# USB_TTL_CH340B.net
KiCad netlist of a schematic drawn in EasyEDA Pro
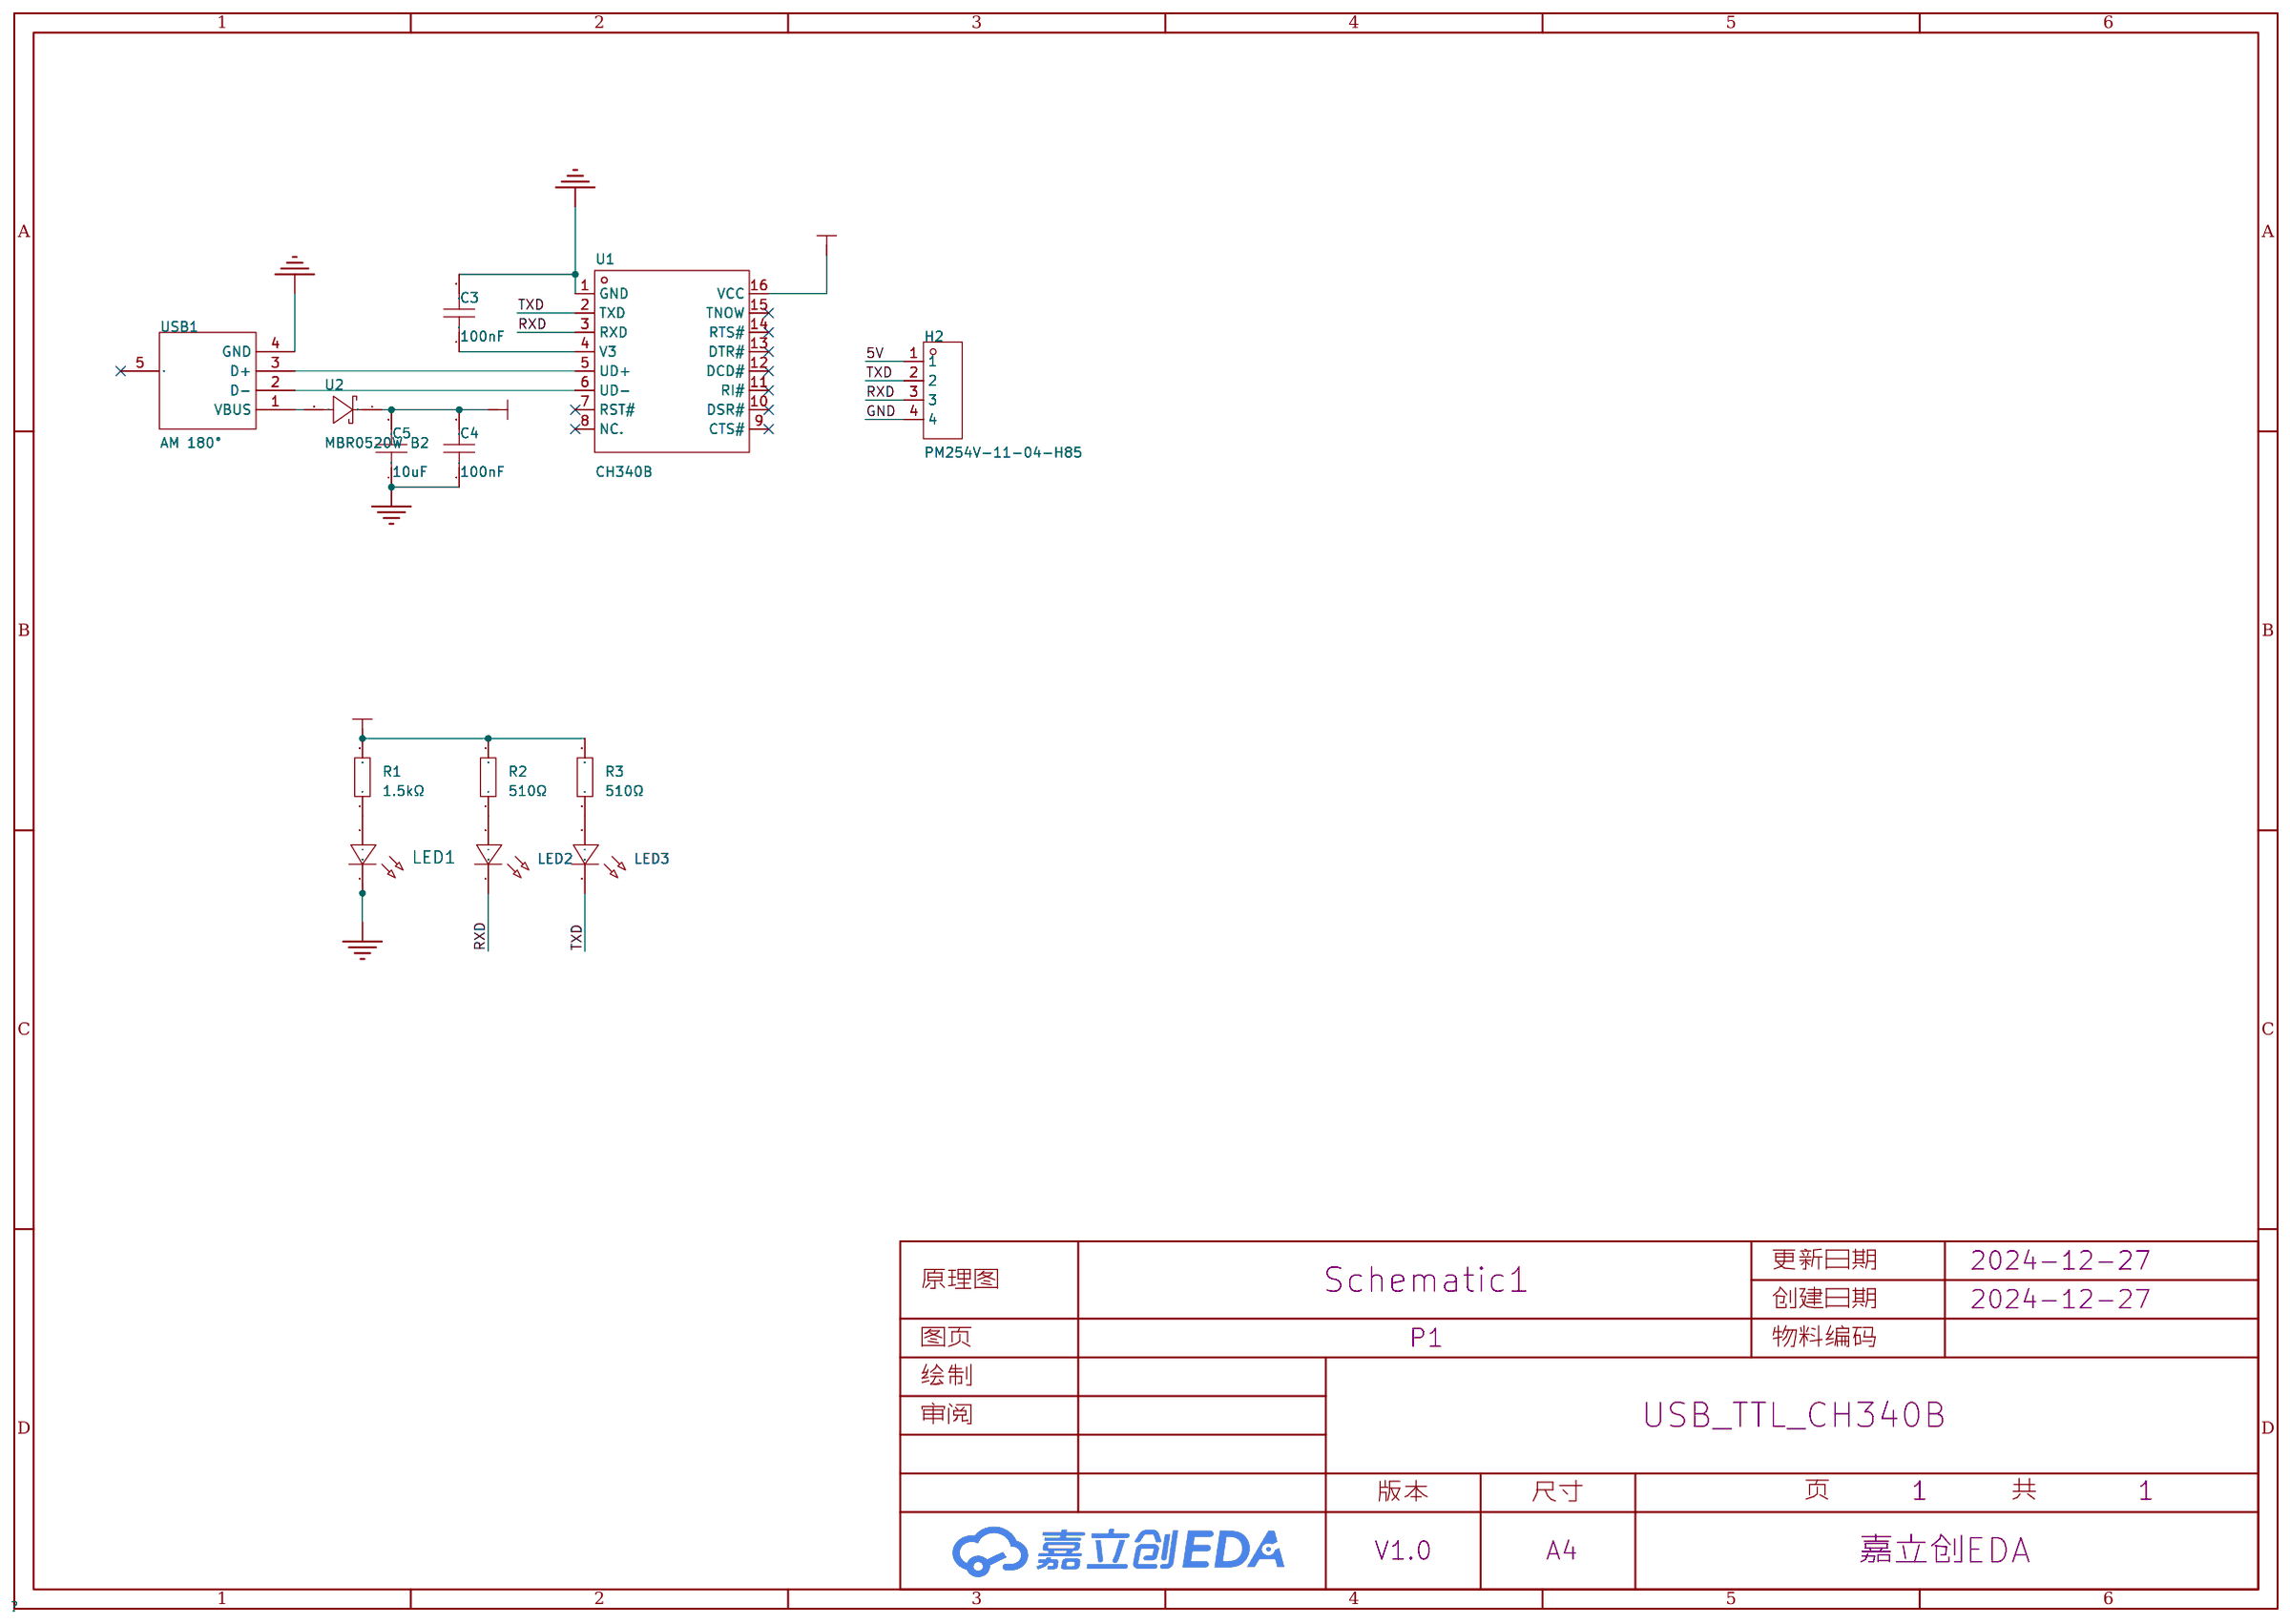
[diagram p0: schematic sheet]

(export (version "E")
  (design (tool "Eeschema 10.0.6"))
  (components
    (comp (ref "C3")
      (value "100nF")
      (footprint "easyedapro:C0603")
      (description "容值:100nF;精度:±10%;额定电压:50V;材质(温度系数):X7R;")
      (fields
        (field (name "Manufacturer Part") "CC0603KRX7R9BB104")
        (field (name "Manufacturer") "YAGEO(国巨)")
      )
      (libsource (lib "easyedapro") (part "CC0603KRX7R9BB104"))
    )
    (comp (ref "C4")
      (value "100nF")
      (footprint "easyedapro:C0603")
      (description "容值:100nF;精度:±10%;额定电压:50V;材质(温度系数):X7R;")
      (fields
        (field (name "Manufacturer Part") "CC0603KRX7R9BB104")
        (field (name "Manufacturer") "YAGEO(国巨)")
      )
      (libsource (lib "easyedapro") (part "CC0603KRX7R9BB104"))
    )
    (comp (ref "C5")
      (value "10uF")
      (footprint "easyedapro:C0603")
      (description "容值:100nF;精度:±10%;额定电压:50V;材质(温度系数):X7R;")
      (fields
        (field (name "Manufacturer Part") "CC0603KRX7R9BB104")
        (field (name "Manufacturer") "YAGEO(国巨)")
      )
      (libsource (lib "easyedapro") (part "CC0603KRX7R9BB104"))
    )
    (comp (ref "H2")
      (value "PM254V-11-04-H85")
      (footprint "easyedapro:HDR-TH_4P-P2.54-V-F")
      (description "间距:2.54mm;总孔位数:4;排数:1;插孔结构:1x4P;行距:-;安装类型:直插;塑高:-;触头材质:黄铜;触头镀层:-;")
      (fields (field (name "Manufacturer") "XFCN(兴飞)"))
      (libsource (lib "easyedapro") (part "PM254V-11-04-H85"))
    )
    (comp (ref "LED1")
      (value "~")
      (footprint "easyedapro:LED_0603")
      (libsource (lib "easyedapro") (part "LED_R"))
    )
    (comp (ref "LED2")
      (value "~")
      (footprint "easyedapro:LED_0603")
      (libsource (lib "easyedapro") (part "LED_G"))
    )
    (comp (ref "LED3")
      (value "~")
      (footprint "easyedapro:LED_0603")
      (libsource (lib "easyedapro") (part "LED_B"))
    )
    (comp (ref "R1")
      (value "1.5kΩ")
      (footprint "easyedapro:R0603")
      (description "电阻类型:厚膜电阻;阻值:1.5kΩ;精度:±1%;功率:100mW;最大工作电压:75V;温度系数:±100ppm/°C;")
      (fields (field (name "Manufacturer Part") "AF0603FR-071K5L") (field (name "Manufacturer") "YAGEO(国巨)"))
      (libsource (lib "easyedapro") (part "AF0603FR-071K5L"))
    )
    (comp (ref "R2")
      (value "510Ω")
      (footprint "easyedapro:R0603")
      (description "电阻类型:厚膜电阻;阻值:1.5kΩ;精度:±1%;功率:100mW;最大工作电压:75V;温度系数:±100ppm/°C;")
      (fields (field (name "Manufacturer Part") "AF0603FR-071K5L") (field (name "Manufacturer") "YAGEO(国巨)"))
      (libsource (lib "easyedapro") (part "AF0603FR-071K5L"))
    )
    (comp (ref "R3")
      (value "510Ω")
      (footprint "easyedapro:R0603")
      (description "电阻类型:厚膜电阻;阻值:1.5kΩ;精度:±1%;功率:100mW;最大工作电压:75V;温度系数:±100ppm/°C;")
      (fields (field (name "Manufacturer Part") "AF0603FR-071K5L") (field (name "Manufacturer") "YAGEO(国巨)"))
      (libsource (lib "easyedapro") (part "AF0603FR-071K5L"))
    )
    (comp (ref "U1")
      (value "CH340B")
      (footprint "easyedapro:SOIC-16_L9.9-W3.9-P1.27-LS6.0-BL")
      (description "应用功能:收发器;接口协议:USB 2.0;数据速率:2Mbps;")
      (fields (field (name "Manufacturer") "WCH(南京沁恒)"))
      (libsource (lib "easyedapro") (part "CH340B"))
    )
    (comp (ref "U2")
      (value "MBR0520W B2")
      (footprint "easyedapro:SOD-123_L2.7-W1.7-LS3.8-RD")
      (fields (field (name "Manufacturer") "Slkor(萨科微)"))
      (libsource (lib "easyedapro") (part "MBR0520W B2"))
    )
    (comp (ref "USB1")
      (value "AM 180°")
      (footprint "easyedapro:USB-SMD_AM180")
      (description "连接器类型:Type-A;标准:USB 2.0;公母:公;安装方式:卧贴;触点数量:4P;端口数量:1;额定电流 - 电源:1.5A;工作温度范围:-25°C~+85°C;")
      (fields (field (name "Manufacturer") "SHOU HAN(首韩)"))
      (libsource (lib "easyedapro") (part "AM 180°"))
    )
  )
  (nets
    (net (code "1") (name "/RXD") (class "Default")
      (node (ref "H2") (pin "3") (pinfunction "3_3") (pintype "input"))
      (node (ref "LED2") (pin "1") (pinfunction "C_1") (pintype "input"))
      (node (ref "U1") (pin "3") (pinfunction "RXD_3") (pintype "unspecified"))
    )
    (net (code "2") (name "/TXD") (class "Default")
      (node (ref "H2") (pin "2") (pinfunction "2_2") (pintype "input"))
      (node (ref "LED3") (pin "1") (pinfunction "C_1") (pintype "input"))
      (node (ref "U1") (pin "2") (pinfunction "TXD_2") (pintype "unspecified"))
    )
    (net (code "3") (name "5V") (class "Default")
      (node (ref "C4") (pin "2") (pinfunction "2_2") (pintype "unspecified"))
      (node (ref "C5") (pin "2") (pinfunction "2_2") (pintype "unspecified"))
      (node (ref "H2") (pin "1") (pinfunction "1_1") (pintype "input"))
      (node (ref "R1") (pin "2") (pinfunction "2_2") (pintype "input"))
      (node (ref "R2") (pin "2") (pinfunction "2_2") (pintype "input"))
      (node (ref "R3") (pin "2") (pinfunction "2_2") (pintype "input"))
      (node (ref "U1") (pin "16") (pinfunction "VCC_16") (pintype "unspecified"))
      (node (ref "U2") (pin "1") (pinfunction "C_1") (pintype "unspecified"))
    )
    (net (code "4") (name "GND") (class "Default")
      (node (ref "C3") (pin "2") (pinfunction "2_2") (pintype "unspecified"))
      (node (ref "C4") (pin "1") (pinfunction "1_1") (pintype "unspecified"))
      (node (ref "C5") (pin "1") (pinfunction "1_1") (pintype "unspecified"))
      (node (ref "H2") (pin "4") (pinfunction "4_4") (pintype "input"))
      (node (ref "LED1") (pin "1") (pinfunction "C_1") (pintype "input"))
      (node (ref "U1") (pin "1") (pinfunction "GND_1") (pintype "unspecified"))
      (node (ref "USB1") (pin "4") (pinfunction "GND_4") (pintype "input"))
    )
    (net (code "5") (name "Net-(LED1-A)") (class "Default")
      (node (ref "LED1") (pin "2") (pinfunction "A_2") (pintype "input"))
      (node (ref "R1") (pin "1") (pinfunction "1_1") (pintype "input"))
    )
    (net (code "6") (name "Net-(LED2-A)") (class "Default")
      (node (ref "LED2") (pin "2") (pinfunction "A_2") (pintype "input"))
      (node (ref "R2") (pin "1") (pinfunction "1_1") (pintype "input"))
    )
    (net (code "7") (name "Net-(LED3-A)") (class "Default")
      (node (ref "LED3") (pin "2") (pinfunction "A_2") (pintype "input"))
      (node (ref "R3") (pin "1") (pinfunction "1_1") (pintype "input"))
    )
    (net (code "8") (name "Net-(U1-UD+)") (class "Default")
      (node (ref "U1") (pin "5") (pinfunction "UD+_5") (pintype "unspecified"))
      (node (ref "USB1") (pin "3") (pinfunction "D+_3") (pintype "input"))
    )
    (net (code "9") (name "Net-(U1-UD-)") (class "Default")
      (node (ref "U1") (pin "6") (pinfunction "UD-_6") (pintype "unspecified"))
      (node (ref "USB1") (pin "2") (pinfunction "D-_2") (pintype "input"))
    )
    (net (code "10") (name "Net-(U1-V3)") (class "Default")
      (node (ref "C3") (pin "1") (pinfunction "1_1") (pintype "unspecified"))
      (node (ref "U1") (pin "4") (pinfunction "V3_4") (pintype "unspecified"))
    )
    (net (code "11") (name "Net-(U2-A)") (class "Default")
      (node (ref "U2") (pin "2") (pinfunction "A_2") (pintype "unspecified"))
      (node (ref "USB1") (pin "1") (pinfunction "VBUS_1") (pintype "input"))
    )
    (net (code "12") (name "unconnected-(U1-CTS#-Pad9)") (class "Default")
      (node (ref "U1") (pin "9") (pinfunction "CTS#_9") (pintype "unspecified+no_connect"))
    )
    (net (code "13") (name "unconnected-(U1-DCD#-Pad12)") (class "Default")
      (node (ref "U1") (pin "12") (pinfunction "DCD#_12") (pintype "unspecified+no_connect"))
    )
    (net (code "14") (name "unconnected-(U1-DSR#-Pad10)") (class "Default")
      (node (ref "U1") (pin "10") (pinfunction "DSR#_10") (pintype "unspecified+no_connect"))
    )
    (net (code "15") (name "unconnected-(U1-DTR#-Pad13)") (class "Default")
      (node (ref "U1") (pin "13") (pinfunction "DTR#_13") (pintype "unspecified+no_connect"))
    )
    (net (code "16") (name "unconnected-(U1-NC.-Pad8)") (class "Default")
      (node (ref "U1") (pin "8") (pinfunction "NC._8") (pintype "unspecified+no_connect"))
    )
    (net (code "17") (name "unconnected-(U1-RI#-Pad11)") (class "Default")
      (node (ref "U1") (pin "11") (pinfunction "RI#_11") (pintype "unspecified+no_connect"))
    )
    (net (code "18") (name "unconnected-(U1-RST#-Pad7)") (class "Default")
      (node (ref "U1") (pin "7") (pinfunction "RST#_7") (pintype "unspecified+no_connect"))
    )
    (net (code "19") (name "unconnected-(U1-RTS#-Pad14)") (class "Default")
      (node (ref "U1") (pin "14") (pinfunction "RTS#_14") (pintype "unspecified+no_connect"))
    )
    (net (code "20") (name "unconnected-(U1-TNOW-Pad15)") (class "Default")
      (node (ref "U1") (pin "15") (pinfunction "TNOW_15") (pintype "unspecified+no_connect"))
    )
    (net (code "21") (name "unconnected-(USB1-EH-Pad5)") (class "Default")
      (node (ref "USB1") (pin "5") (pinfunction "EH_5") (pintype "input+no_connect"))
    )
  )
)
